# Digital.net
KiCad netlist of a schematic drawn in Altium Designer
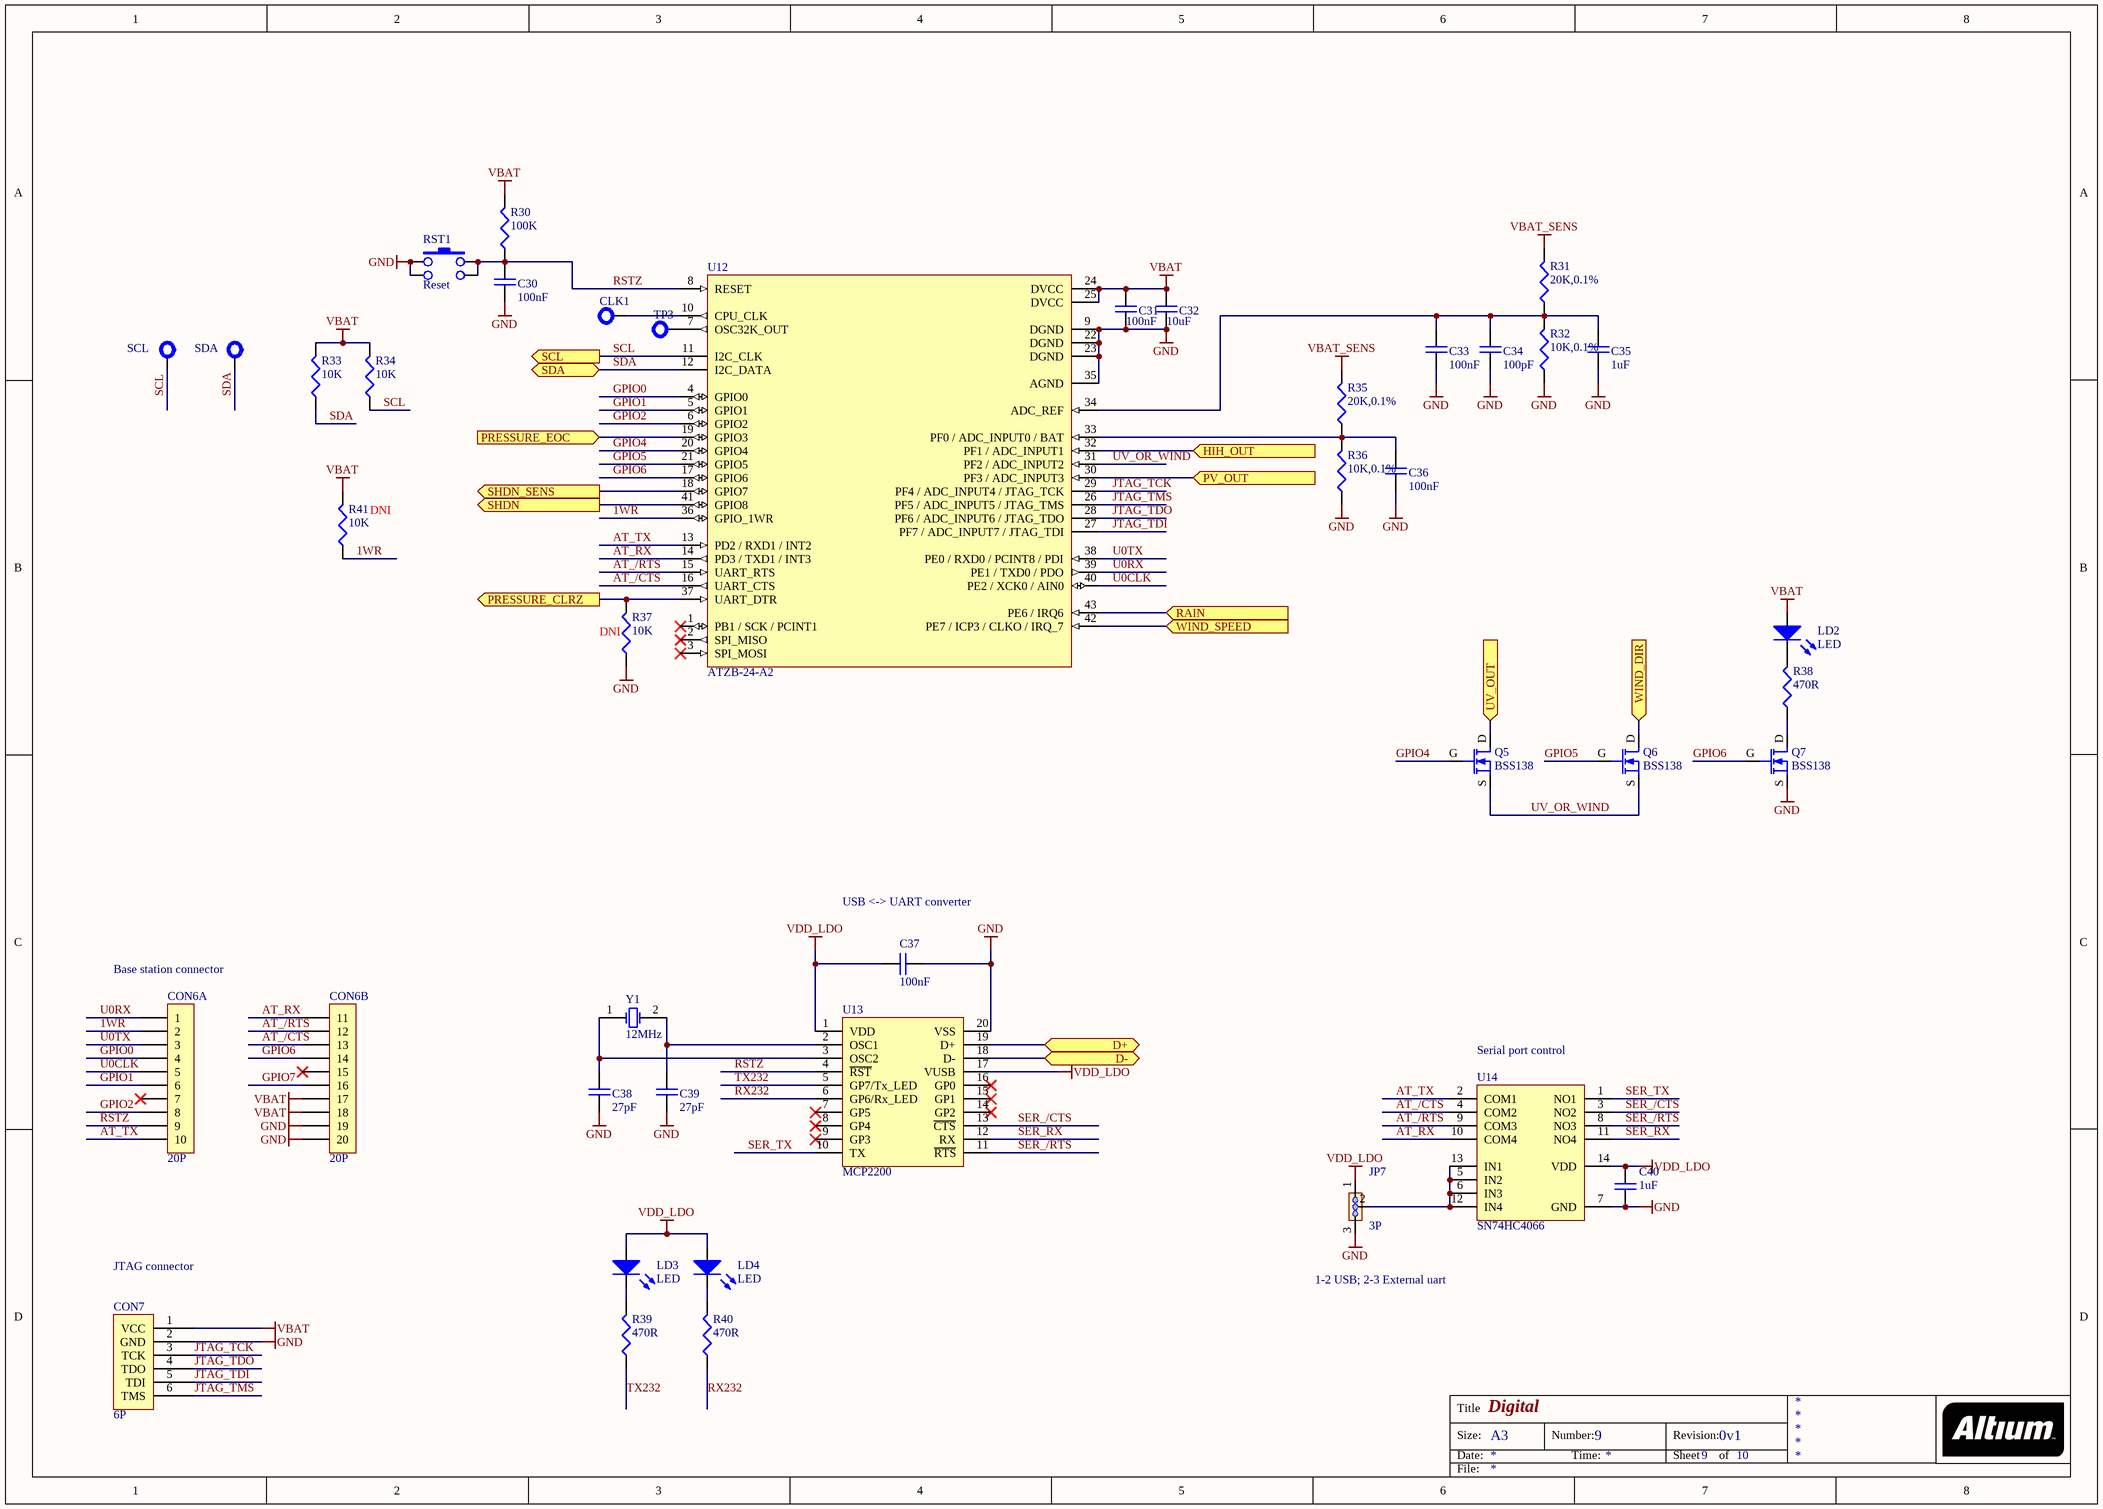
[diagram p0: Digital.SchDoc]

(export (version "E")
  (design (tool "Eeschema 10.0.6"))
  (components
    (comp (ref "C30")
      (value "100nF")
      (footprint "0603")
      (description "Capacitor")
      (fields (field (name "OWNER") "Nuno Brum"))
      (libsource (lib "Alcetronics_Devices") (part "CAP"))
    )
    (comp (ref "C31")
      (value "100nF")
      (footprint "0603")
      (description "Capacitor")
      (fields (field (name "OWNER") "Nuno Brum"))
      (libsource (lib "Alcetronics_Devices") (part "CAP"))
    )
    (comp (ref "C32")
      (value "10uF")
      (footprint "0805")
      (description "Capacitor")
      (fields (field (name "OWNER") "Nuno Brum"))
      (libsource (lib "Alcetronics_Devices") (part "CAP"))
    )
    (comp (ref "C33")
      (value "100nF")
      (footprint "0603")
      (description "Capacitor")
      (fields (field (name "OWNER") "Nuno Brum"))
      (libsource (lib "Alcetronics_Devices") (part "CAP"))
    )
    (comp (ref "C34")
      (value "100pF")
      (footprint "0603")
      (description "Capacitor")
      (fields (field (name "OWNER") "Nuno Brum"))
      (libsource (lib "Alcetronics_Devices") (part "CAP"))
    )
    (comp (ref "C35")
      (value "1uF")
      (footprint "0603")
      (description "Capacitor")
      (fields (field (name "OWNER") "Nuno Brum"))
      (libsource (lib "Alcetronics_Devices") (part "CAP"))
    )
    (comp (ref "C36")
      (value "100nF")
      (footprint "0603")
      (description "Capacitor")
      (fields (field (name "OWNER") "Nuno Brum"))
      (libsource (lib "Alcetronics_Devices") (part "CAP"))
    )
    (comp (ref "C37")
      (value "100nF")
      (footprint "0603")
      (description "Capacitor")
      (fields (field (name "OWNER") "Nuno Brum"))
      (libsource (lib "Alcetronics_Devices") (part "CAP"))
    )
    (comp (ref "C38")
      (value "27pF")
      (footprint "0603")
      (description "Capacitor")
      (fields (field (name "OWNER") "Nuno Brum"))
      (libsource (lib "Alcetronics_Devices") (part "CAP"))
    )
    (comp (ref "C39")
      (value "27pF")
      (footprint "0603")
      (description "Capacitor")
      (fields (field (name "OWNER") "Nuno Brum"))
      (libsource (lib "Alcetronics_Devices") (part "CAP"))
    )
    (comp (ref "C40")
      (value "1uF")
      (footprint "0603")
      (description "Capacitor")
      (fields (field (name "OWNER") "Nuno Brum"))
      (libsource (lib "Alcetronics_Devices") (part "CAP"))
    )
    (comp (ref "CLK1")
      (value "Test Point")
      (footprint "TERMINAL")
      (description "Test/Probe Point")
      (fields (field (name "OWNER") "Nuno Brum"))
      (libsource (lib "Alcetronics_EM") (part "TEST-PROBE"))
    )
    (comp (ref "CON6")
      (value "20P")
      (footprint "IDC-20")
      (description "Connector 20 Pins")
      (fields (field (name "OWNER") "Nuno Brum"))
      (libsource (lib "Alcetronics_EM") (part "CON20"))
    )
    (comp (ref "CON7")
      (value "6P")
      (footprint "SIP-6-JTAG")
      (description "Generic JTAG Connector")
      (fields (field (name "OWNER") "António Oliveira"))
      (libsource (lib "Alcetronics_EM") (part "CON-JTAG"))
    )
    (comp (ref "JP7")
      (value "3P")
      (footprint "SIP-3")
      (description "3-Jumper")
      (fields (field (name "OWNER") "Nuno Brum"))
      (libsource (lib "Alcetronics_EM") (part "JMP3"))
    )
    (comp (ref "LD2")
      (value "LED")
      (footprint "0805@DIODE")
      (description "Light emitting diode")
      (fields (field (name "OWNER") "Nuno Brum"))
      (libsource (lib "Alcetronics_Devices") (part "LED"))
    )
    (comp (ref "LD3")
      (value "LED")
      (footprint "0805@DIODE")
      (description "Light emitting diode")
      (fields (field (name "OWNER") "Nuno Brum"))
      (libsource (lib "Alcetronics_Devices") (part "LED"))
    )
    (comp (ref "LD4")
      (value "LED")
      (footprint "0805@DIODE")
      (description "Light emitting diode")
      (fields (field (name "OWNER") "Nuno Brum"))
      (libsource (lib "Alcetronics_Devices") (part "LED"))
    )
    (comp (ref "Q5")
      (value "BSS138")
      (footprint "SOT-23@GSD")
      (description "N-Channel Logic Level Enhancement Mode Field Effect Transistor")
      (fields (field (name "OWNER") "Nuno Brum"))
      (libsource (lib "Alcetronics_Devices") (part "MOSFET-N"))
    )
    (comp (ref "Q6")
      (value "BSS138")
      (footprint "SOT-23@GSD")
      (description "N-Channel Logic Level Enhancement Mode Field Effect Transistor")
      (fields (field (name "OWNER") "Nuno Brum"))
      (libsource (lib "Alcetronics_Devices") (part "MOSFET-N"))
    )
    (comp (ref "Q7")
      (value "BSS138")
      (footprint "SOT-23@GSD")
      (description "N-Channel Logic Level Enhancement Mode Field Effect Transistor")
      (fields (field (name "OWNER") "Nuno Brum"))
      (libsource (lib "Alcetronics_Devices") (part "MOSFET-N"))
    )
    (comp (ref "R30")
      (value "100K")
      (footprint "0603")
      (description "Resistor")
      (fields (field (name "OWNER") "Nuno Brum"))
      (libsource (lib "Alcetronics_Devices") (part "RES"))
    )
    (comp (ref "R31")
      (value "20K,0.1%")
      (footprint "0603")
      (description "Resistor")
      (fields (field (name "OWNER") "Nuno Brum"))
      (libsource (lib "Alcetronics_Devices") (part "RES"))
    )
    (comp (ref "R32")
      (value "10K,0.1%")
      (footprint "0603")
      (description "Resistor")
      (fields (field (name "OWNER") "Nuno Brum"))
      (libsource (lib "Alcetronics_Devices") (part "RES"))
    )
    (comp (ref "R33")
      (value "10K")
      (footprint "0603")
      (description "Resistor")
      (fields (field (name "OWNER") "Nuno Brum"))
      (libsource (lib "Alcetronics_Devices") (part "RES"))
    )
    (comp (ref "R34")
      (value "10K")
      (footprint "0603")
      (description "Resistor")
      (fields (field (name "OWNER") "Nuno Brum"))
      (libsource (lib "Alcetronics_Devices") (part "RES"))
    )
    (comp (ref "R35")
      (value "20K,0.1%")
      (footprint "0603")
      (description "Resistor")
      (fields (field (name "OWNER") "Nuno Brum"))
      (libsource (lib "Alcetronics_Devices") (part "RES"))
    )
    (comp (ref "R36")
      (value "10K,0.1%")
      (footprint "0603")
      (description "Resistor")
      (fields (field (name "OWNER") "Nuno Brum"))
      (libsource (lib "Alcetronics_Devices") (part "RES"))
    )
    (comp (ref "R37")
      (value "10K")
      (footprint "0603")
      (description "Resistor")
      (fields (field (name "OWNER") "Nuno Brum"))
      (libsource (lib "Alcetronics_Devices") (part "RES"))
    )
    (comp (ref "R38")
      (value "470R")
      (footprint "0603")
      (description "Resistor")
      (fields (field (name "OWNER") "Nuno Brum"))
      (libsource (lib "Alcetronics_Devices") (part "RES"))
    )
    (comp (ref "R39")
      (value "470R")
      (footprint "0603")
      (description "Resistor")
      (fields (field (name "OWNER") "Nuno Brum"))
      (libsource (lib "Alcetronics_Devices") (part "RES"))
    )
    (comp (ref "R40")
      (value "470R")
      (footprint "0603")
      (description "Resistor")
      (fields (field (name "OWNER") "Nuno Brum"))
      (libsource (lib "Alcetronics_Devices") (part "RES"))
    )
    (comp (ref "R41")
      (value "10K")
      (footprint "0603")
      (description "Resistor")
      (fields (field (name "OWNER") "Nuno Brum"))
      (libsource (lib "Alcetronics_Devices") (part "RES"))
    )
    (comp (ref "RST1")
      (value "Reset")
      (footprint "MICROSWITCH")
      (description "Switch Push Button")
      (fields (field (name "OWNER") "Nuno Brum"))
      (libsource (lib "Alcetronics_EM") (part "SW1"))
    )
    (comp (ref "SCL")
      (value "Test Point")
      (footprint "TERMINAL")
      (description "Test/Probe Point")
      (fields (field (name "OWNER") "Nuno Brum"))
      (libsource (lib "Alcetronics_EM") (part "TEST-PROBE"))
    )
    (comp (ref "SDA")
      (value "Test Point")
      (footprint "TERMINAL")
      (description "Test/Probe Point")
      (fields (field (name "OWNER") "Nuno Brum"))
      (libsource (lib "Alcetronics_EM") (part "TEST-PROBE"))
    )
    (comp (ref "TP3")
      (value "Test Point")
      (footprint "TERMINAL")
      (description "Test/Probe Point")
      (fields (field (name "OWNER") "Nuno Brum"))
      (libsource (lib "Alcetronics_EM") (part "TEST-PROBE"))
    )
    (comp (ref "U12")
      (value "ATZB-24-A2")
      (footprint "ATZB-24-A2")
      (description "Zigbee Module")
      (libsource (lib "Alcetronics_IC") (part "ATZB-24-A2"))
    )
    (comp (ref "U13")
      (value "MCP2200")
      (footprint "SOIC-20")
      (description "USB to Serial interface")
      (fields (field (name "PUBLISHER") "Altium Limited"))
      (libsource (lib "Alcetronics_IC") (part "MCP2200"))
    )
    (comp (ref "U14")
      (value "SN74HC4066")
      (footprint "TSSOP-14")
      (description "4 analog switch (normally open)")
      (libsource (lib "Alcetronics_IC") (part "MAX4751"))
    )
    (comp (ref "Y1")
      (value "12MHz")
      (footprint "CSM-7")
      (description "Crystal Oscillator")
      (fields (field (name "PUBLISHER") "Altium Limited"))
      (libsource (lib "Alcetronics_Devices") (part "Crystal Oscillator"))
    )
  )
  (nets
    (net (code "1") (name "/1WR") (class "Default")
      (node (ref "CON6") (pin "2") (pinfunction "2_2") (pintype "passive"))
      (node (ref "R41") (pin "1") (pinfunction "1_1") (pintype "passive"))
      (node (ref "U12") (pin "36") (pinfunction "GPIO_1WR_36") (pintype "bidirectional"))
    )
    (net (code "2") (name "/AT_RX") (class "Default")
      (node (ref "CON6") (pin "11") (pinfunction "11_11") (pintype "passive"))
      (node (ref "U12") (pin "14") (pinfunction "PD3_/_TXD1_/_INT3_14") (pintype "output"))
      (node (ref "U14") (pin "10") (pinfunction "COM4_10") (pintype "passive"))
    )
    (net (code "3") (name "/AT_TX") (class "Default")
      (node (ref "CON6") (pin "10") (pinfunction "10_10") (pintype "passive"))
      (node (ref "U12") (pin "13") (pinfunction "PD2_/_RXD1_/_INT2_13") (pintype "input"))
      (node (ref "U14") (pin "2") (pinfunction "COM1_2") (pintype "passive"))
    )
    (net (code "4") (name "/AT_{slash}CTS") (class "Default")
      (node (ref "CON6") (pin "13") (pinfunction "13_13") (pintype "passive"))
      (node (ref "U12") (pin "16") (pinfunction "UART_CTS_16") (pintype "output"))
      (node (ref "U14") (pin "4") (pinfunction "COM2_4") (pintype "passive"))
    )
    (net (code "5") (name "/AT_{slash}RTS") (class "Default")
      (node (ref "CON6") (pin "12") (pinfunction "12_12") (pintype "passive"))
      (node (ref "U12") (pin "15") (pinfunction "UART_RTS_15") (pintype "input"))
      (node (ref "U14") (pin "9") (pinfunction "COM3_9") (pintype "passive"))
    )
    (net (code "6") (name "/D+") (class "Default")
      (node (ref "U13") (pin "19") (pinfunction "D+_19") (pintype "passive"))
    )
    (net (code "7") (name "/D-") (class "Default")
      (node (ref "U13") (pin "18") (pinfunction "D-_18") (pintype "passive"))
    )
    (net (code "8") (name "/GPIO0") (class "Default")
      (node (ref "CON6") (pin "4") (pinfunction "4_4") (pintype "passive"))
      (node (ref "U12") (pin "4") (pinfunction "GPIO0_4") (pintype "bidirectional"))
    )
    (net (code "9") (name "/GPIO1") (class "Default")
      (node (ref "CON6") (pin "6") (pinfunction "6_6") (pintype "passive"))
      (node (ref "U12") (pin "5") (pinfunction "GPIO1_5") (pintype "bidirectional"))
    )
    (net (code "10") (name "/GPIO2") (class "Default")
      (node (ref "CON6") (pin "8") (pinfunction "8_8") (pintype "passive"))
      (node (ref "U12") (pin "6") (pinfunction "GPIO2_6") (pintype "bidirectional"))
    )
    (net (code "11") (name "/GPIO4") (class "Default")
      (node (ref "Q5") (pin "G") (pinfunction "G_G") (pintype "passive"))
      (node (ref "U12") (pin "20") (pinfunction "GPIO4_20") (pintype "bidirectional"))
    )
    (net (code "12") (name "/GPIO5") (class "Default")
      (node (ref "Q6") (pin "G") (pinfunction "G_G") (pintype "passive"))
      (node (ref "U12") (pin "21") (pinfunction "GPIO5_21") (pintype "bidirectional"))
    )
    (net (code "13") (name "/GPIO6") (class "Default")
      (node (ref "CON6") (pin "14") (pinfunction "14_14") (pintype "passive"))
      (node (ref "Q7") (pin "G") (pinfunction "G_G") (pintype "passive"))
      (node (ref "U12") (pin "17") (pinfunction "GPIO6_17") (pintype "bidirectional"))
    )
    (net (code "14") (name "/GPIO7") (class "Default")
      (node (ref "CON6") (pin "16") (pinfunction "16_16") (pintype "passive"))
    )
    (net (code "15") (name "/HIH_OUT") (class "Default")
      (node (ref "U12") (pin "32") (pinfunction "PF1_/_ADC_INPUT1_32") (pintype "input"))
    )
    (net (code "16") (name "/JTAG_TCK") (class "Default")
      (node (ref "CON7") (pin "3") (pinfunction "TCK_3") (pintype "passive"))
      (node (ref "U12") (pin "29") (pinfunction "PF4_/_ADC_INPUT4_/_JTAG_TCK_29") (pintype "open_collector"))
    )
    (net (code "17") (name "/JTAG_TDI") (class "Default")
      (node (ref "CON7") (pin "5") (pinfunction "TDI_5") (pintype "passive"))
      (node (ref "U12") (pin "27") (pinfunction "PF7_/_ADC_INPUT7_/_JTAG_TDI_27") (pintype "open_collector"))
    )
    (net (code "18") (name "/JTAG_TDO") (class "Default")
      (node (ref "CON7") (pin "4") (pinfunction "TDO_4") (pintype "passive"))
      (node (ref "U12") (pin "28") (pinfunction "PF6_/_ADC_INPUT6_/_JTAG_TDO_28") (pintype "open_collector"))
    )
    (net (code "19") (name "/JTAG_TMS") (class "Default")
      (node (ref "CON7") (pin "6") (pinfunction "TMS_6") (pintype "passive"))
      (node (ref "U12") (pin "26") (pinfunction "PF5_/_ADC_INPUT5_/_JTAG_TMS_26") (pintype "open_collector"))
    )
    (net (code "20") (name "/PRESSURE_CLRZ") (class "Default")
      (node (ref "R37") (pin "2") (pinfunction "2_2") (pintype "passive"))
      (node (ref "U12") (pin "37") (pinfunction "UART_DTR_37") (pintype "input"))
    )
    (net (code "21") (name "/PRESSURE_EOC") (class "Default")
      (node (ref "U12") (pin "19") (pinfunction "GPIO3_19") (pintype "bidirectional"))
    )
    (net (code "22") (name "/PV_OUT") (class "Default")
      (node (ref "U12") (pin "30") (pinfunction "PF3_/_ADC_INPUT3_30") (pintype "input"))
    )
    (net (code "23") (name "/RAIN") (class "Default")
      (node (ref "U12") (pin "43") (pinfunction "PE6_/_IRQ6_43") (pintype "input"))
    )
    (net (code "24") (name "/RSTZ") (class "Default")
      (node (ref "C30") (pin "2") (pinfunction "2_2") (pintype "passive"))
      (node (ref "CON6") (pin "9") (pinfunction "9_9") (pintype "passive"))
      (node (ref "R30") (pin "1") (pinfunction "1_1") (pintype "passive"))
      (node (ref "RST1") (pin "2") (pinfunction "2_2") (pintype "passive"))
      (node (ref "RST1") (pin "4") (pinfunction "4_4") (pintype "passive"))
      (node (ref "U12") (pin "8") (pinfunction "RESET_8") (pintype "input"))
      (node (ref "U13") (pin "4") (pinfunction "~{RST}_4") (pintype "passive"))
    )
    (net (code "25") (name "/RX232") (class "Default")
      (node (ref "R40") (pin "1") (pinfunction "1_1") (pintype "passive"))
      (node (ref "U13") (pin "6") (pinfunction "GP6/Rx_LED_6") (pintype "passive"))
    )
    (net (code "26") (name "/SCL") (class "Default")
      (node (ref "R34") (pin "1") (pinfunction "1_1") (pintype "passive"))
      (node (ref "SCL") (pin "1") (pinfunction "TP_1") (pintype "passive"))
      (node (ref "U12") (pin "11") (pinfunction "I2C_CLK_11") (pintype "open_collector"))
    )
    (net (code "27") (name "/SDA") (class "Default")
      (node (ref "R33") (pin "1") (pinfunction "1_1") (pintype "passive"))
      (node (ref "SDA") (pin "1") (pinfunction "TP_1") (pintype "passive"))
      (node (ref "U12") (pin "12") (pinfunction "I2C_DATA_12") (pintype "open_collector"))
    )
    (net (code "28") (name "/SER_RX") (class "Default")
      (node (ref "U13") (pin "12") (pinfunction "RX_12") (pintype "passive"))
      (node (ref "U14") (pin "11") (pinfunction "NO4_11") (pintype "passive"))
    )
    (net (code "29") (name "/SER_TX") (class "Default")
      (node (ref "U13") (pin "10") (pinfunction "TX_10") (pintype "passive"))
      (node (ref "U14") (pin "1") (pinfunction "NO1_1") (pintype "passive"))
    )
    (net (code "30") (name "/SER_{slash}CTS") (class "Default")
      (node (ref "U13") (pin "13") (pinfunction "~{CTS}_13") (pintype "passive"))
      (node (ref "U14") (pin "3") (pinfunction "NO2_3") (pintype "passive"))
    )
    (net (code "31") (name "/SER_{slash}RTS") (class "Default")
      (node (ref "U13") (pin "11") (pinfunction "~{RTS}_11") (pintype "passive"))
      (node (ref "U14") (pin "8") (pinfunction "NO3_8") (pintype "passive"))
    )
    (net (code "32") (name "/SHDN") (class "Default")
      (node (ref "U12") (pin "41") (pinfunction "GPIO8_41") (pintype "bidirectional"))
    )
    (net (code "33") (name "/SHDN_SENS") (class "Default")
      (node (ref "U12") (pin "18") (pinfunction "GPIO7_18") (pintype "bidirectional"))
    )
    (net (code "34") (name "/TX232") (class "Default")
      (node (ref "R39") (pin "1") (pinfunction "1_1") (pintype "passive"))
      (node (ref "U13") (pin "5") (pinfunction "GP7/Tx_LED_5") (pintype "passive"))
    )
    (net (code "35") (name "/U0CLK") (class "Default")
      (node (ref "CON6") (pin "5") (pinfunction "5_5") (pintype "passive"))
      (node (ref "U12") (pin "40") (pinfunction "PE2_/_XCK0_/_AIN0_40") (pintype "bidirectional"))
    )
    (net (code "36") (name "/U0RX") (class "Default")
      (node (ref "CON6") (pin "1") (pinfunction "1_1") (pintype "passive"))
      (node (ref "U12") (pin "39") (pinfunction "PE1_/_TXD0_/_PDO_39") (pintype "output"))
    )
    (net (code "37") (name "/U0TX") (class "Default")
      (node (ref "CON6") (pin "3") (pinfunction "3_3") (pintype "passive"))
      (node (ref "U12") (pin "38") (pinfunction "PE0_/_RXD0_/_PCINT8_/_PDI_38") (pintype "input"))
    )
    (net (code "38") (name "/UV_OR_WIND") (class "Default")
      (node (ref "Q5") (pin "S") (pinfunction "S_S") (pintype "passive"))
      (node (ref "Q6") (pin "S") (pinfunction "S_S") (pintype "passive"))
      (node (ref "U12") (pin "31") (pinfunction "PF2_/_ADC_INPUT2_31") (pintype "input"))
    )
    (net (code "39") (name "/UV_OUT") (class "Default")
      (node (ref "Q5") (pin "D") (pinfunction "D_D") (pintype "passive"))
    )
    (net (code "40") (name "/WIND_DIR") (class "Default")
      (node (ref "Q6") (pin "D") (pinfunction "D_D") (pintype "passive"))
    )
    (net (code "41") (name "/WIND_SPEED") (class "Default")
      (node (ref "U12") (pin "42") (pinfunction "PE7_/_ICP3_/_CLKO_/_IRQ_7_42") (pintype "input"))
    )
    (net (code "42") (name "GND") (class "Default")
      (node (ref "C30") (pin "1") (pinfunction "1_1") (pintype "passive"))
      (node (ref "C31") (pin "1") (pinfunction "1_1") (pintype "passive"))
      (node (ref "C32") (pin "1") (pinfunction "1_1") (pintype "passive"))
      (node (ref "C33") (pin "1") (pinfunction "1_1") (pintype "passive"))
      (node (ref "C34") (pin "1") (pinfunction "1_1") (pintype "passive"))
      (node (ref "C35") (pin "1") (pinfunction "1_1") (pintype "passive"))
      (node (ref "C36") (pin "1") (pinfunction "1_1") (pintype "passive"))
      (node (ref "C37") (pin "1") (pinfunction "1_1") (pintype "passive"))
      (node (ref "C38") (pin "1") (pinfunction "1_1") (pintype "passive"))
      (node (ref "C39") (pin "1") (pinfunction "1_1") (pintype "passive"))
      (node (ref "C40") (pin "1") (pinfunction "1_1") (pintype "passive"))
      (node (ref "CON6") (pin "19") (pinfunction "19_19") (pintype "passive"))
      (node (ref "CON6") (pin "20") (pinfunction "20_20") (pintype "passive"))
      (node (ref "CON7") (pin "2") (pinfunction "GND_2") (pintype "passive"))
      (node (ref "JP7") (pin "3") (pinfunction "3_3") (pintype "passive"))
      (node (ref "Q7") (pin "S") (pinfunction "S_S") (pintype "passive"))
      (node (ref "R32") (pin "1") (pinfunction "1_1") (pintype "passive"))
      (node (ref "R36") (pin "1") (pinfunction "1_1") (pintype "passive"))
      (node (ref "R37") (pin "1") (pinfunction "1_1") (pintype "passive"))
      (node (ref "RST1") (pin "1") (pinfunction "1_1") (pintype "passive"))
      (node (ref "RST1") (pin "3") (pinfunction "3_3") (pintype "passive"))
      (node (ref "U12") (pin "22") (pinfunction "DGND_22") (pintype "power_in"))
      (node (ref "U12") (pin "23") (pinfunction "DGND_23") (pintype "power_in"))
      (node (ref "U12") (pin "35") (pinfunction "AGND_35") (pintype "power_in"))
      (node (ref "U12") (pin "9") (pinfunction "DGND_9") (pintype "power_in"))
      (node (ref "U13") (pin "20") (pinfunction "VSS_20") (pintype "power_in"))
      (node (ref "U14") (pin "7") (pinfunction "GND_7") (pintype "passive"))
    )
    (net (code "43") (name "Net-(CLK1-TP)") (class "Default")
      (node (ref "CLK1") (pin "1") (pinfunction "TP_1") (pintype "passive"))
      (node (ref "U12") (pin "10") (pinfunction "CPU_CLK_10") (pintype "output"))
    )
    (net (code "44") (name "Net-(LD2-PadK)") (class "Default")
      (node (ref "LD2") (pin "K") (pinfunction "K_K") (pintype "passive"))
      (node (ref "R38") (pin "2") (pinfunction "2_2") (pintype "passive"))
    )
    (net (code "45") (name "Net-(LD3-PadK)") (class "Default")
      (node (ref "LD3") (pin "K") (pinfunction "K_K") (pintype "passive"))
      (node (ref "R39") (pin "2") (pinfunction "2_2") (pintype "passive"))
    )
    (net (code "46") (name "Net-(LD4-PadK)") (class "Default")
      (node (ref "LD4") (pin "K") (pinfunction "K_K") (pintype "passive"))
      (node (ref "R40") (pin "2") (pinfunction "2_2") (pintype "passive"))
    )
    (net (code "47") (name "Net-(Q7-PadD)") (class "Default")
      (node (ref "Q7") (pin "D") (pinfunction "D_D") (pintype "passive"))
      (node (ref "R38") (pin "1") (pinfunction "1_1") (pintype "passive"))
    )
    (net (code "48") (name "Net-(TP3-TP)") (class "Default")
      (node (ref "TP3") (pin "1") (pinfunction "TP_1") (pintype "passive"))
      (node (ref "U12") (pin "7") (pinfunction "OSC32K_OUT_7") (pintype "output"))
    )
    (net (code "49") (name "Net-(U12-ADC_REF)") (class "Default")
      (node (ref "C33") (pin "2") (pinfunction "2_2") (pintype "passive"))
      (node (ref "C34") (pin "2") (pinfunction "2_2") (pintype "passive"))
      (node (ref "C35") (pin "2") (pinfunction "2_2") (pintype "passive"))
      (node (ref "R31") (pin "1") (pinfunction "1_1") (pintype "passive"))
      (node (ref "R32") (pin "2") (pinfunction "2_2") (pintype "passive"))
      (node (ref "U12") (pin "34") (pinfunction "ADC_REF_34") (pintype "input"))
    )
    (net (code "50") (name "Net-(U12-PF0_{slash}_ADC_INPUT0_{slash}_BAT)") (class "Default")
      (node (ref "C36") (pin "2") (pinfunction "2_2") (pintype "passive"))
      (node (ref "R35") (pin "1") (pinfunction "1_1") (pintype "passive"))
      (node (ref "R36") (pin "2") (pinfunction "2_2") (pintype "passive"))
      (node (ref "U12") (pin "33") (pinfunction "PF0_/_ADC_INPUT0_/_BAT_33") (pintype "input"))
    )
    (net (code "51") (name "Net-(U13-OSC1)") (class "Default")
      (node (ref "C39") (pin "2") (pinfunction "2_2") (pintype "passive"))
      (node (ref "U13") (pin "2") (pinfunction "OSC1_2") (pintype "passive"))
      (node (ref "Y1") (pin "2") (pinfunction "OSC2_2") (pintype "passive"))
    )
    (net (code "52") (name "Net-(U13-OSC2)") (class "Default")
      (node (ref "C38") (pin "2") (pinfunction "2_2") (pintype "passive"))
      (node (ref "U13") (pin "3") (pinfunction "OSC2_3") (pintype "passive"))
      (node (ref "Y1") (pin "1") (pinfunction "OSC1_1") (pintype "passive"))
    )
    (net (code "53") (name "Net-(U14-IN1)") (class "Default")
      (node (ref "JP7") (pin "2") (pinfunction "2_2") (pintype "passive"))
      (node (ref "U14") (pin "12") (pinfunction "IN4_12") (pintype "passive"))
      (node (ref "U14") (pin "13") (pinfunction "IN1_13") (pintype "passive"))
      (node (ref "U14") (pin "5") (pinfunction "IN2_5") (pintype "passive"))
      (node (ref "U14") (pin "6") (pinfunction "IN3_6") (pintype "passive"))
    )
    (net (code "54") (name "VBAT") (class "Default")
      (node (ref "C31") (pin "2") (pinfunction "2_2") (pintype "passive"))
      (node (ref "C32") (pin "2") (pinfunction "2_2") (pintype "passive"))
      (node (ref "CON6") (pin "17") (pinfunction "17_17") (pintype "passive"))
      (node (ref "CON6") (pin "18") (pinfunction "18_18") (pintype "passive"))
      (node (ref "CON7") (pin "1") (pinfunction "VCC_1") (pintype "passive"))
      (node (ref "LD2") (pin "A") (pinfunction "A_A") (pintype "passive"))
      (node (ref "R30") (pin "2") (pinfunction "2_2") (pintype "passive"))
      (node (ref "R33") (pin "2") (pinfunction "2_2") (pintype "passive"))
      (node (ref "R34") (pin "2") (pinfunction "2_2") (pintype "passive"))
      (node (ref "R41") (pin "2") (pinfunction "2_2") (pintype "passive"))
      (node (ref "U12") (pin "24") (pinfunction "DVCC_24") (pintype "power_in"))
      (node (ref "U12") (pin "25") (pinfunction "DVCC_25") (pintype "power_in"))
    )
    (net (code "55") (name "VBAT_SENS") (class "Default")
      (node (ref "R31") (pin "2") (pinfunction "2_2") (pintype "passive"))
      (node (ref "R35") (pin "2") (pinfunction "2_2") (pintype "passive"))
    )
    (net (code "56") (name "VDD_LDO") (class "Default")
      (node (ref "C37") (pin "2") (pinfunction "2_2") (pintype "passive"))
      (node (ref "C40") (pin "2") (pinfunction "2_2") (pintype "passive"))
      (node (ref "JP7") (pin "1") (pinfunction "1_1") (pintype "passive"))
      (node (ref "LD3") (pin "A") (pinfunction "A_A") (pintype "passive"))
      (node (ref "LD4") (pin "A") (pinfunction "A_A") (pintype "passive"))
      (node (ref "U13") (pin "1") (pinfunction "VDD_1") (pintype "power_in"))
      (node (ref "U13") (pin "17") (pinfunction "VUSB_17") (pintype "power_in"))
      (node (ref "U14") (pin "14") (pinfunction "VDD_14") (pintype "passive"))
    )
    (net (code "57") (name "unconnected-(CON6-Pad7)") (class "Default")
      (node (ref "CON6") (pin "7") (pinfunction "7_7") (pintype "passive+no_connect"))
    )
    (net (code "58") (name "unconnected-(CON6-Pad15)") (class "Default")
      (node (ref "CON6") (pin "15") (pinfunction "15_15") (pintype "passive+no_connect"))
    )
    (net (code "59") (name "unconnected-(U12-PB1_{slash}_SCK_{slash}_PCINT1-Pad1)") (class "Default")
      (node (ref "U12") (pin "1") (pinfunction "PB1_/_SCK_/_PCINT1_1") (pintype "bidirectional+no_connect"))
    )
    (net (code "60") (name "unconnected-(U12-SPI_MISO-Pad2)") (class "Default")
      (node (ref "U12") (pin "2") (pinfunction "SPI_MISO_2") (pintype "output+no_connect"))
    )
    (net (code "61") (name "unconnected-(U12-SPI_MOSI-Pad3)") (class "Default")
      (node (ref "U12") (pin "3") (pinfunction "SPI_MOSI_3") (pintype "input+no_connect"))
    )
    (net (code "62") (name "unconnected-(U13-GP0-Pad16)") (class "Default")
      (node (ref "U13") (pin "16") (pinfunction "GP0_16") (pintype "passive+no_connect"))
    )
    (net (code "63") (name "unconnected-(U13-GP1-Pad15)") (class "Default")
      (node (ref "U13") (pin "15") (pinfunction "GP1_15") (pintype "passive+no_connect"))
    )
    (net (code "64") (name "unconnected-(U13-GP2-Pad14)") (class "Default")
      (node (ref "U13") (pin "14") (pinfunction "GP2_14") (pintype "passive+no_connect"))
    )
    (net (code "65") (name "unconnected-(U13-GP3-Pad9)") (class "Default")
      (node (ref "U13") (pin "9") (pinfunction "GP3_9") (pintype "passive+no_connect"))
    )
    (net (code "66") (name "unconnected-(U13-GP4-Pad8)") (class "Default")
      (node (ref "U13") (pin "8") (pinfunction "GP4_8") (pintype "passive+no_connect"))
    )
    (net (code "67") (name "unconnected-(U13-GP5-Pad7)") (class "Default")
      (node (ref "U13") (pin "7") (pinfunction "GP5_7") (pintype "passive+no_connect"))
    )
  )
)
